# Curing_cab.net
KiCad netlist of a schematic drawn in EAGLE
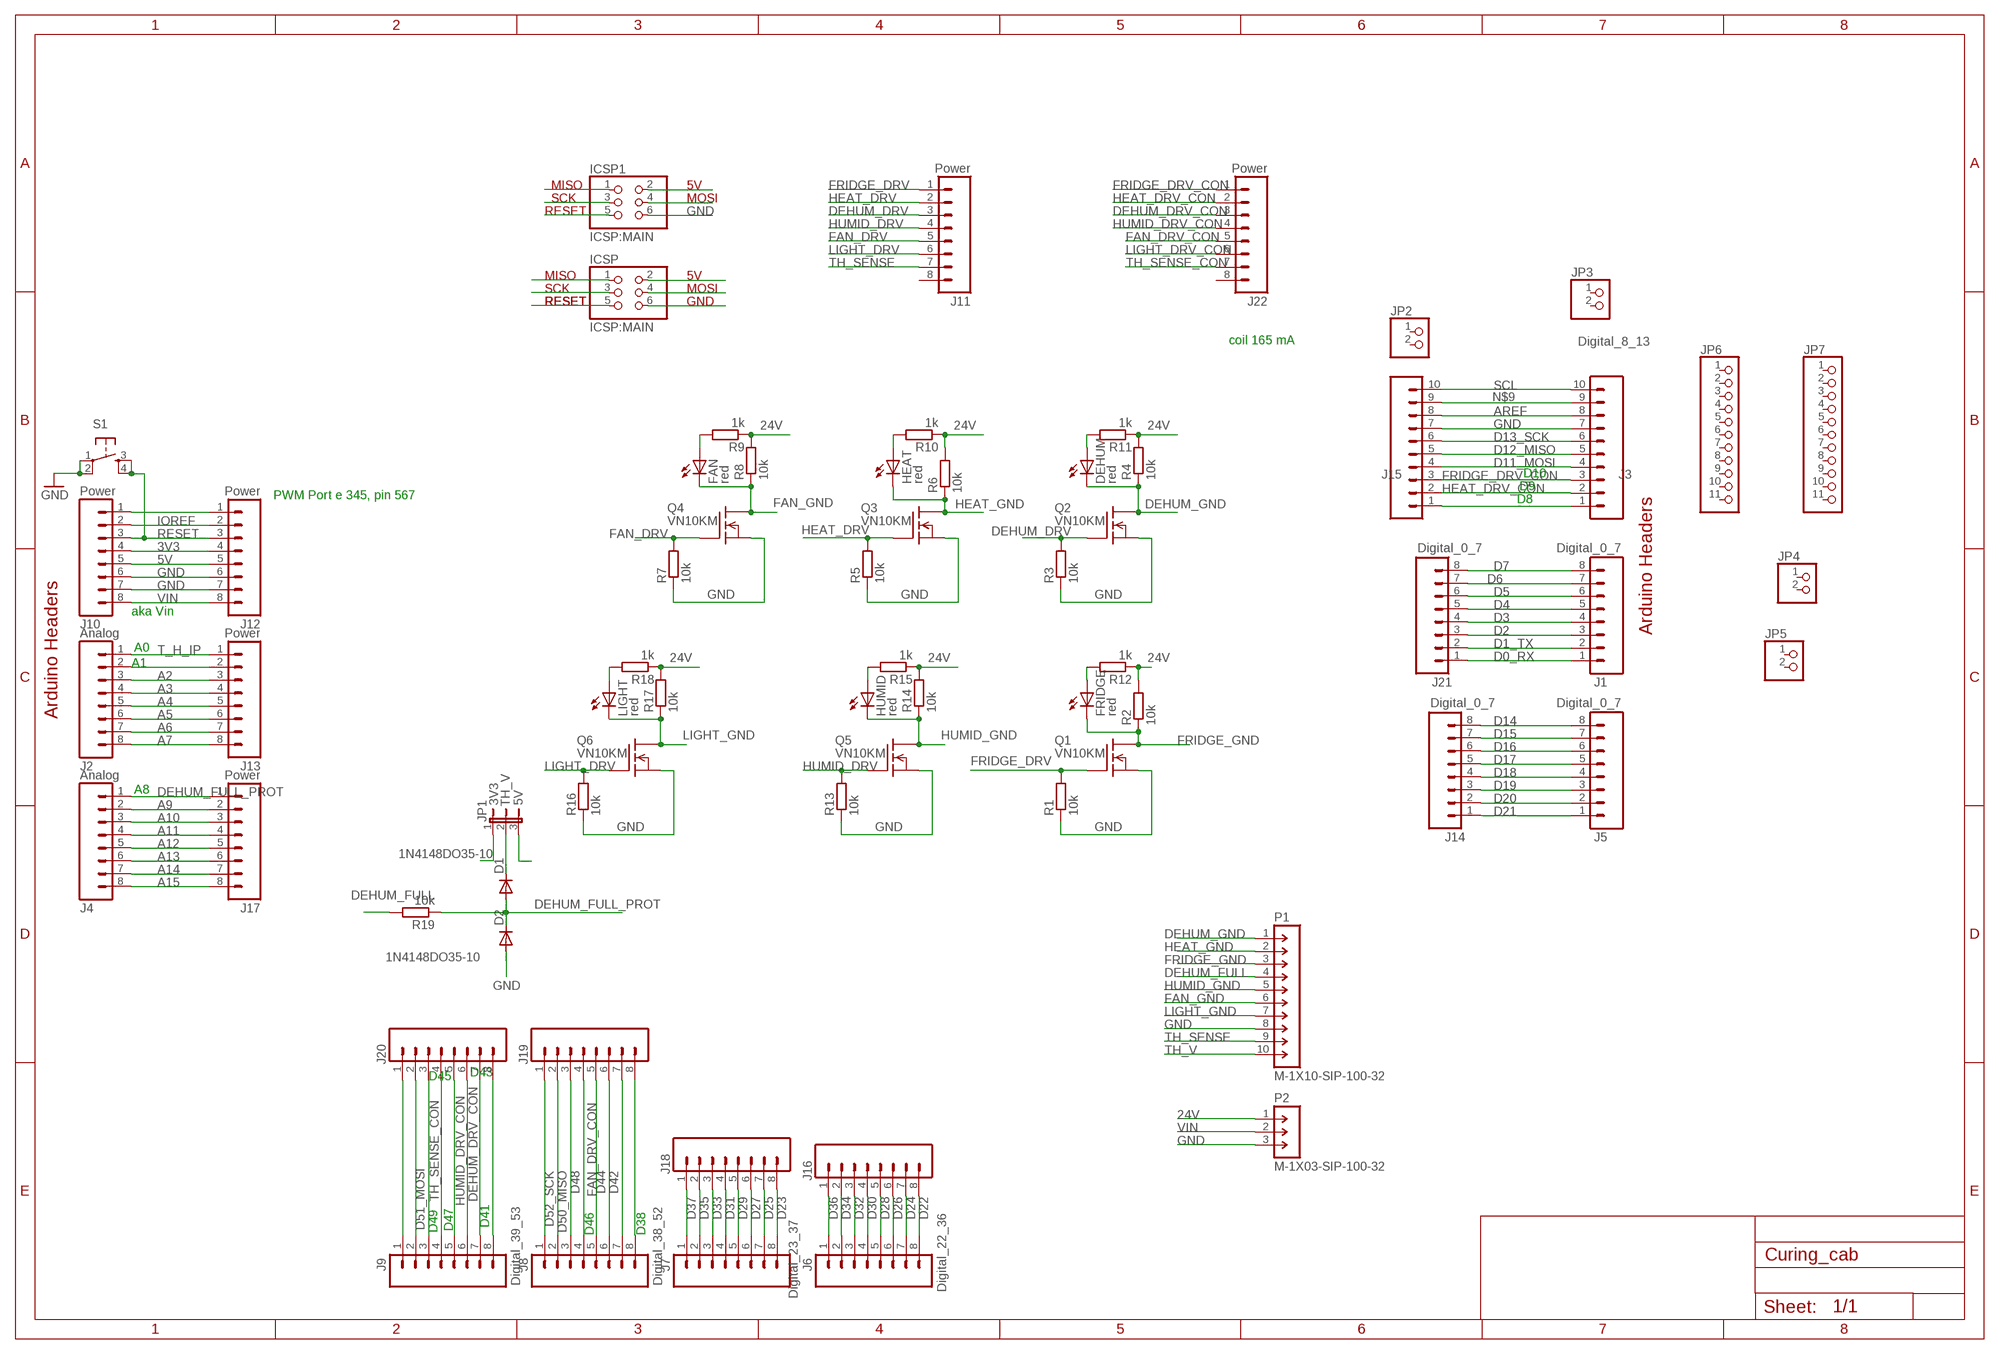
[diagram p0: schematic, sheet 1]

(export (version "E")
  (design (tool "Eeschema 10.0.6"))
  (components
    (comp (ref "D1")
      (value "1N4148DO35-10")
      (footprint "eagle-import:DO35-10")
      (libsource (lib "eagle-import") (part "1N4148DO35-10"))
    )
    (comp (ref "D2")
      (value "1N4148DO35-10")
      (footprint "eagle-import:DO35-10")
      (libsource (lib "eagle-import") (part "1N4148DO35-10"))
    )
    (comp (ref "DEHUM")
      (value "red")
      (footprint "eagle-import:LED3MM")
      (libsource (lib "eagle-import") (part "LED3MM"))
    )
    (comp (ref "FAN")
      (value "red")
      (footprint "eagle-import:LED3MM")
      (libsource (lib "eagle-import") (part "LED3MM"))
    )
    (comp (ref "FRIDGE")
      (value "red")
      (footprint "eagle-import:LED3MM")
      (libsource (lib "eagle-import") (part "LED3MM"))
    )
    (comp (ref "HEAT")
      (value "red")
      (footprint "eagle-import:LED3MM")
      (libsource (lib "eagle-import") (part "LED3MM"))
    )
    (comp (ref "HUMID")
      (value "red")
      (footprint "eagle-import:LED3MM")
      (libsource (lib "eagle-import") (part "LED3MM"))
    )
    (comp (ref "ICSP")
      (value "ICSP:MAIN")
      (footprint "eagle-import:2X03")
      (libsource (lib "eagle-import") (part "PINHD-2X3"))
    )
    (comp (ref "ICSP1")
      (value "ICSP:MAIN")
      (footprint "eagle-import:2X03")
      (libsource (lib "eagle-import") (part "PINHD-2X3"))
    )
    (comp (ref "J1")
      (value "Digital_0_7")
      (footprint "eagle-import:1X08")
      (libsource (lib "eagle-import") (part "M08"))
    )
    (comp (ref "J2")
      (value "Analog")
      (footprint "eagle-import:1X08")
      (libsource (lib "eagle-import") (part "freetronics-master-v1_M08"))
    )
    (comp (ref "J3")
      (value "Digital_8_13")
      (footprint "eagle-import:1X10")
      (libsource (lib "eagle-import") (part "M100.1"))
    )
    (comp (ref "J4")
      (value "Analog")
      (footprint "eagle-import:1X08")
      (libsource (lib "eagle-import") (part "freetronics-master-v1_M08"))
    )
    (comp (ref "J5")
      (value "Digital_0_7")
      (footprint "eagle-import:1X08")
      (libsource (lib "eagle-import") (part "M08"))
    )
    (comp (ref "J6")
      (value "Digital_22_36")
      (footprint "eagle-import:1X08")
      (libsource (lib "eagle-import") (part "M08"))
    )
    (comp (ref "J7")
      (value "Digital_23_37")
      (footprint "eagle-import:1X08")
      (libsource (lib "eagle-import") (part "M08"))
    )
    (comp (ref "J8")
      (value "Digital_38_52")
      (footprint "eagle-import:1X08")
      (libsource (lib "eagle-import") (part "M08"))
    )
    (comp (ref "J9")
      (value "Digital_39_53")
      (footprint "eagle-import:1X08")
      (libsource (lib "eagle-import") (part "M08"))
    )
    (comp (ref "J10")
      (value "Power")
      (footprint "eagle-import:1X08")
      (libsource (lib "eagle-import") (part "freetronics-master-v1_M08"))
    )
    (comp (ref "J11")
      (value "Power")
      (footprint "eagle-import:1X08")
      (libsource (lib "eagle-import") (part "freetronics-master-v1_M08"))
    )
    (comp (ref "J12")
      (value "Power")
      (footprint "eagle-import:1X08")
      (libsource (lib "eagle-import") (part "freetronics-master-v1_M08"))
    )
    (comp (ref "J13")
      (value "Power")
      (footprint "eagle-import:1X08")
      (libsource (lib "eagle-import") (part "freetronics-master-v1_M08"))
    )
    (comp (ref "J14")
      (value "Digital_0_7")
      (footprint "eagle-import:1X08")
      (libsource (lib "eagle-import") (part "M08"))
    )
    (comp (ref "J15")
      (value "Digital_8_13")
      (footprint "eagle-import:1X10")
      (libsource (lib "eagle-import") (part "M100.1"))
    )
    (comp (ref "J16")
      (value "Digital_22_36")
      (footprint "eagle-import:1X08")
      (libsource (lib "eagle-import") (part "M08"))
    )
    (comp (ref "J17")
      (value "Power")
      (footprint "eagle-import:1X08")
      (libsource (lib "eagle-import") (part "freetronics-master-v1_M08"))
    )
    (comp (ref "J18")
      (value "Digital_22_36")
      (footprint "eagle-import:1X08")
      (libsource (lib "eagle-import") (part "M08"))
    )
    (comp (ref "J19")
      (value "Digital_22_36")
      (footprint "eagle-import:1X08")
      (libsource (lib "eagle-import") (part "M08"))
    )
    (comp (ref "J20")
      (value "Digital_22_36")
      (footprint "eagle-import:1X08")
      (libsource (lib "eagle-import") (part "M08"))
    )
    (comp (ref "J21")
      (value "Digital_0_7")
      (footprint "eagle-import:1X08")
      (libsource (lib "eagle-import") (part "M08"))
    )
    (comp (ref "J22")
      (value "Power")
      (footprint "eagle-import:1X08")
      (libsource (lib "eagle-import") (part "freetronics-master-v1_M08"))
    )
    (comp (ref "JP1")
      (value "JP2E")
      (footprint "eagle-import:JP2")
      (libsource (lib "eagle-import") (part "JP2E"))
    )
    (comp (ref "JP2")
      (value "PINHD-1X2")
      (footprint "eagle-import:1X02")
      (libsource (lib "eagle-import") (part "PINHD-1X2"))
    )
    (comp (ref "JP3")
      (value "PINHD-1X2")
      (footprint "eagle-import:1X02")
      (libsource (lib "eagle-import") (part "PINHD-1X2"))
    )
    (comp (ref "JP4")
      (value "PINHD-1X2")
      (footprint "eagle-import:1X02")
      (libsource (lib "eagle-import") (part "PINHD-1X2"))
    )
    (comp (ref "JP5")
      (value "PINHD-1X2")
      (footprint "eagle-import:1X02")
      (libsource (lib "eagle-import") (part "PINHD-1X2"))
    )
    (comp (ref "JP6")
      (value "PINHD-1X11")
      (footprint "eagle-import:1X11")
      (libsource (lib "eagle-import") (part "PINHD-1X11"))
    )
    (comp (ref "JP7")
      (value "PINHD-1X11")
      (footprint "eagle-import:1X11")
      (libsource (lib "eagle-import") (part "PINHD-1X11"))
    )
    (comp (ref "LIGHT")
      (value "red")
      (footprint "eagle-import:LED3MM")
      (libsource (lib "eagle-import") (part "LED3MM"))
    )
    (comp (ref "P1")
      (value "M-1X10-SIP-100-32")
      (footprint "eagle-import:SIP-100-10-32")
      (libsource (lib "eagle-import") (part "M-1X10-SIP-100-32"))
    )
    (comp (ref "P2")
      (value "M-1X03-SIP-100-32")
      (footprint "eagle-import:SIP-100-03-32")
      (libsource (lib "eagle-import") (part "M-1X03-SIP-100-32"))
    )
    (comp (ref "Q1")
      (value "VN10KM")
      (footprint "eagle-import:TO237")
      (libsource (lib "eagle-import") (part "VN10KM"))
    )
    (comp (ref "Q2")
      (value "VN10KM")
      (footprint "eagle-import:TO237")
      (libsource (lib "eagle-import") (part "VN10KM"))
    )
    (comp (ref "Q3")
      (value "VN10KM")
      (footprint "eagle-import:TO237")
      (libsource (lib "eagle-import") (part "VN10KM"))
    )
    (comp (ref "Q4")
      (value "VN10KM")
      (footprint "eagle-import:TO237")
      (libsource (lib "eagle-import") (part "VN10KM"))
    )
    (comp (ref "Q5")
      (value "VN10KM")
      (footprint "eagle-import:TO237")
      (libsource (lib "eagle-import") (part "VN10KM"))
    )
    (comp (ref "Q6")
      (value "VN10KM")
      (footprint "eagle-import:TO237")
      (libsource (lib "eagle-import") (part "VN10KM"))
    )
    (comp (ref "R1")
      (value "10k")
      (footprint "eagle-import:0204_7")
      (libsource (lib "eagle-import") (part "R-EU_0204/7"))
    )
    (comp (ref "R2")
      (value "10k")
      (footprint "eagle-import:0204_7")
      (libsource (lib "eagle-import") (part "R-EU_0204/7"))
    )
    (comp (ref "R3")
      (value "10k")
      (footprint "eagle-import:0204_7")
      (libsource (lib "eagle-import") (part "R-EU_0204/7"))
    )
    (comp (ref "R4")
      (value "10k")
      (footprint "eagle-import:0204_7")
      (libsource (lib "eagle-import") (part "R-EU_0204/7"))
    )
    (comp (ref "R5")
      (value "10k")
      (footprint "eagle-import:0204_7")
      (libsource (lib "eagle-import") (part "R-EU_0204/7"))
    )
    (comp (ref "R6")
      (value "10k")
      (footprint "eagle-import:0204_7")
      (libsource (lib "eagle-import") (part "R-EU_0204/7"))
    )
    (comp (ref "R7")
      (value "10k")
      (footprint "eagle-import:0204_7")
      (libsource (lib "eagle-import") (part "R-EU_0204/7"))
    )
    (comp (ref "R8")
      (value "10k")
      (footprint "eagle-import:0204_7")
      (libsource (lib "eagle-import") (part "R-EU_0204/7"))
    )
    (comp (ref "R9")
      (value "1k")
      (footprint "eagle-import:0204_7")
      (libsource (lib "eagle-import") (part "R-EU_0204/7"))
    )
    (comp (ref "R10")
      (value "1k")
      (footprint "eagle-import:0204_7")
      (libsource (lib "eagle-import") (part "R-EU_0204/7"))
    )
    (comp (ref "R11")
      (value "1k")
      (footprint "eagle-import:0204_7")
      (libsource (lib "eagle-import") (part "R-EU_0204/7"))
    )
    (comp (ref "R12")
      (value "1k")
      (footprint "eagle-import:0204_7")
      (libsource (lib "eagle-import") (part "R-EU_0204/7"))
    )
    (comp (ref "R13")
      (value "10k")
      (footprint "eagle-import:0204_7")
      (libsource (lib "eagle-import") (part "R-EU_0204/7"))
    )
    (comp (ref "R14")
      (value "10k")
      (footprint "eagle-import:0204_7")
      (libsource (lib "eagle-import") (part "R-EU_0204/7"))
    )
    (comp (ref "R15")
      (value "1k")
      (footprint "eagle-import:0204_7")
      (libsource (lib "eagle-import") (part "R-EU_0204/7"))
    )
    (comp (ref "R16")
      (value "10k")
      (footprint "eagle-import:0204_7")
      (libsource (lib "eagle-import") (part "R-EU_0204/7"))
    )
    (comp (ref "R17")
      (value "10k")
      (footprint "eagle-import:0204_7")
      (libsource (lib "eagle-import") (part "R-EU_0204/7"))
    )
    (comp (ref "R18")
      (value "1k")
      (footprint "eagle-import:0204_7")
      (libsource (lib "eagle-import") (part "R-EU_0204/7"))
    )
    (comp (ref "R19")
      (value "10k")
      (footprint "eagle-import:0204_7")
      (libsource (lib "eagle-import") (part "R-EU_0204/7"))
    )
    (comp (ref "S1")
      (value "TAC_SWITCHPTH")
      (footprint "eagle-import:TACTILE-PTH")
      (libsource (lib "eagle-import") (part "TAC_SWITCHPTH"))
    )
  )
  (nets
    (net (code "1") (name "/3V3") (class "Default")
      (node (ref "J10") (pin "4") (pinfunction "4_4") (pintype "passive"))
      (node (ref "J12") (pin "4") (pinfunction "4_4") (pintype "passive"))
      (node (ref "JP1") (pin "1") (pinfunction "1_1") (pintype "passive"))
    )
    (net (code "2") (name "/5V") (class "Default")
      (node (ref "J10") (pin "5") (pinfunction "5_5") (pintype "passive"))
      (node (ref "J12") (pin "5") (pinfunction "5_5") (pintype "passive"))
      (node (ref "JP1") (pin "3") (pinfunction "3_3") (pintype "passive"))
    )
    (net (code "3") (name "/5V_1") (class "Default")
      (node (ref "ICSP") (pin "2") (pinfunction "2_2") (pintype "passive"))
      (node (ref "ICSP1") (pin "2") (pinfunction "2_2") (pintype "passive"))
    )
    (net (code "4") (name "/24V") (class "Default")
      (node (ref "P2") (pin "1") (pinfunction "1_1") (pintype "passive"))
      (node (ref "R10") (pin "1") (pinfunction "1_1") (pintype "passive"))
      (node (ref "R11") (pin "1") (pinfunction "1_1") (pintype "passive"))
      (node (ref "R12") (pin "1") (pinfunction "1_1") (pintype "passive"))
      (node (ref "R14") (pin "2") (pinfunction "2_2") (pintype "passive"))
      (node (ref "R15") (pin "1") (pinfunction "1_1") (pintype "passive"))
      (node (ref "R17") (pin "2") (pinfunction "2_2") (pintype "passive"))
      (node (ref "R18") (pin "1") (pinfunction "1_1") (pintype "passive"))
      (node (ref "R2") (pin "2") (pinfunction "2_2") (pintype "passive"))
      (node (ref "R4") (pin "2") (pinfunction "2_2") (pintype "passive"))
      (node (ref "R6") (pin "2") (pinfunction "2_2") (pintype "passive"))
      (node (ref "R8") (pin "2") (pinfunction "2_2") (pintype "passive"))
      (node (ref "R9") (pin "1") (pinfunction "1_1") (pintype "passive"))
    )
    (net (code "5") (name "/A2") (class "Default")
      (node (ref "J13") (pin "3") (pinfunction "3_3") (pintype "passive"))
      (node (ref "J2") (pin "3") (pinfunction "3_3") (pintype "passive"))
    )
    (net (code "6") (name "/A3") (class "Default")
      (node (ref "J13") (pin "4") (pinfunction "4_4") (pintype "passive"))
      (node (ref "J2") (pin "4") (pinfunction "4_4") (pintype "passive"))
    )
    (net (code "7") (name "/A4") (class "Default")
      (node (ref "J13") (pin "5") (pinfunction "5_5") (pintype "passive"))
      (node (ref "J2") (pin "5") (pinfunction "5_5") (pintype "passive"))
    )
    (net (code "8") (name "/A5") (class "Default")
      (node (ref "J13") (pin "6") (pinfunction "6_6") (pintype "passive"))
      (node (ref "J2") (pin "6") (pinfunction "6_6") (pintype "passive"))
    )
    (net (code "9") (name "/A6") (class "Default")
      (node (ref "J13") (pin "7") (pinfunction "7_7") (pintype "passive"))
      (node (ref "J2") (pin "7") (pinfunction "7_7") (pintype "passive"))
    )
    (net (code "10") (name "/A7") (class "Default")
      (node (ref "J13") (pin "8") (pinfunction "8_8") (pintype "passive"))
      (node (ref "J2") (pin "8") (pinfunction "8_8") (pintype "passive"))
    )
    (net (code "11") (name "/A9") (class "Default")
      (node (ref "J17") (pin "2") (pinfunction "2_2") (pintype "passive"))
      (node (ref "J4") (pin "2") (pinfunction "2_2") (pintype "passive"))
    )
    (net (code "12") (name "/A10") (class "Default")
      (node (ref "J17") (pin "3") (pinfunction "3_3") (pintype "passive"))
      (node (ref "J4") (pin "3") (pinfunction "3_3") (pintype "passive"))
    )
    (net (code "13") (name "/A11") (class "Default")
      (node (ref "J17") (pin "4") (pinfunction "4_4") (pintype "passive"))
      (node (ref "J4") (pin "4") (pinfunction "4_4") (pintype "passive"))
    )
    (net (code "14") (name "/A12") (class "Default")
      (node (ref "J17") (pin "5") (pinfunction "5_5") (pintype "passive"))
      (node (ref "J4") (pin "5") (pinfunction "5_5") (pintype "passive"))
    )
    (net (code "15") (name "/A13") (class "Default")
      (node (ref "J17") (pin "6") (pinfunction "6_6") (pintype "passive"))
      (node (ref "J4") (pin "6") (pinfunction "6_6") (pintype "passive"))
    )
    (net (code "16") (name "/A14") (class "Default")
      (node (ref "J17") (pin "7") (pinfunction "7_7") (pintype "passive"))
      (node (ref "J4") (pin "7") (pinfunction "7_7") (pintype "passive"))
    )
    (net (code "17") (name "/A15") (class "Default")
      (node (ref "J17") (pin "8") (pinfunction "8_8") (pintype "passive"))
      (node (ref "J4") (pin "8") (pinfunction "8_8") (pintype "passive"))
    )
    (net (code "18") (name "/AREF") (class "Default")
      (node (ref "J15") (pin "8") (pinfunction "8_8") (pintype "passive"))
      (node (ref "J3") (pin "8") (pinfunction "8_8") (pintype "passive"))
    )
    (net (code "19") (name "/D0_RX") (class "Default")
      (node (ref "J1") (pin "1") (pinfunction "1_1") (pintype "passive"))
      (node (ref "J21") (pin "1") (pinfunction "1_1") (pintype "passive"))
    )
    (net (code "20") (name "/D1_TX") (class "Default")
      (node (ref "J1") (pin "2") (pinfunction "2_2") (pintype "passive"))
      (node (ref "J21") (pin "2") (pinfunction "2_2") (pintype "passive"))
    )
    (net (code "21") (name "/D2") (class "Default")
      (node (ref "J1") (pin "3") (pinfunction "3_3") (pintype "passive"))
      (node (ref "J21") (pin "3") (pinfunction "3_3") (pintype "passive"))
    )
    (net (code "22") (name "/D3") (class "Default")
      (node (ref "J1") (pin "4") (pinfunction "4_4") (pintype "passive"))
      (node (ref "J21") (pin "4") (pinfunction "4_4") (pintype "passive"))
    )
    (net (code "23") (name "/D4") (class "Default")
      (node (ref "J1") (pin "5") (pinfunction "5_5") (pintype "passive"))
      (node (ref "J21") (pin "5") (pinfunction "5_5") (pintype "passive"))
    )
    (net (code "24") (name "/D5") (class "Default")
      (node (ref "J1") (pin "6") (pinfunction "6_6") (pintype "passive"))
      (node (ref "J21") (pin "6") (pinfunction "6_6") (pintype "passive"))
    )
    (net (code "25") (name "/D6") (class "Default")
      (node (ref "J1") (pin "7") (pinfunction "7_7") (pintype "passive"))
      (node (ref "J21") (pin "7") (pinfunction "7_7") (pintype "passive"))
    )
    (net (code "26") (name "/D7") (class "Default")
      (node (ref "J1") (pin "8") (pinfunction "8_8") (pintype "passive"))
      (node (ref "J21") (pin "8") (pinfunction "8_8") (pintype "passive"))
    )
    (net (code "27") (name "/D11_MOSI") (class "Default")
      (node (ref "J15") (pin "4") (pinfunction "4_4") (pintype "passive"))
      (node (ref "J3") (pin "4") (pinfunction "4_4") (pintype "passive"))
    )
    (net (code "28") (name "/D12_MISO") (class "Default")
      (node (ref "J15") (pin "5") (pinfunction "5_5") (pintype "passive"))
      (node (ref "J3") (pin "5") (pinfunction "5_5") (pintype "passive"))
    )
    (net (code "29") (name "/D13_SCK") (class "Default")
      (node (ref "J15") (pin "6") (pinfunction "6_6") (pintype "passive"))
      (node (ref "J3") (pin "6") (pinfunction "6_6") (pintype "passive"))
    )
    (net (code "30") (name "/D14") (class "Default")
      (node (ref "J14") (pin "8") (pinfunction "8_8") (pintype "passive"))
      (node (ref "J5") (pin "8") (pinfunction "8_8") (pintype "passive"))
    )
    (net (code "31") (name "/D15") (class "Default")
      (node (ref "J14") (pin "7") (pinfunction "7_7") (pintype "passive"))
      (node (ref "J5") (pin "7") (pinfunction "7_7") (pintype "passive"))
    )
    (net (code "32") (name "/D16") (class "Default")
      (node (ref "J14") (pin "6") (pinfunction "6_6") (pintype "passive"))
      (node (ref "J5") (pin "6") (pinfunction "6_6") (pintype "passive"))
    )
    (net (code "33") (name "/D17") (class "Default")
      (node (ref "J14") (pin "5") (pinfunction "5_5") (pintype "passive"))
      (node (ref "J5") (pin "5") (pinfunction "5_5") (pintype "passive"))
    )
    (net (code "34") (name "/D18") (class "Default")
      (node (ref "J14") (pin "4") (pinfunction "4_4") (pintype "passive"))
      (node (ref "J5") (pin "4") (pinfunction "4_4") (pintype "passive"))
    )
    (net (code "35") (name "/D19") (class "Default")
      (node (ref "J14") (pin "3") (pinfunction "3_3") (pintype "passive"))
      (node (ref "J5") (pin "3") (pinfunction "3_3") (pintype "passive"))
    )
    (net (code "36") (name "/D20") (class "Default")
      (node (ref "J14") (pin "2") (pinfunction "2_2") (pintype "passive"))
      (node (ref "J5") (pin "2") (pinfunction "2_2") (pintype "passive"))
    )
    (net (code "37") (name "/D21") (class "Default")
      (node (ref "J14") (pin "1") (pinfunction "1_1") (pintype "passive"))
      (node (ref "J5") (pin "1") (pinfunction "1_1") (pintype "passive"))
    )
    (net (code "38") (name "/D22") (class "Default")
      (node (ref "J16") (pin "8") (pinfunction "8_8") (pintype "passive"))
      (node (ref "J6") (pin "8") (pinfunction "8_8") (pintype "passive"))
    )
    (net (code "39") (name "/D23") (class "Default")
      (node (ref "J18") (pin "8") (pinfunction "8_8") (pintype "passive"))
      (node (ref "J7") (pin "8") (pinfunction "8_8") (pintype "passive"))
    )
    (net (code "40") (name "/D24") (class "Default")
      (node (ref "J16") (pin "7") (pinfunction "7_7") (pintype "passive"))
      (node (ref "J6") (pin "7") (pinfunction "7_7") (pintype "passive"))
    )
    (net (code "41") (name "/D25") (class "Default")
      (node (ref "J18") (pin "7") (pinfunction "7_7") (pintype "passive"))
      (node (ref "J7") (pin "7") (pinfunction "7_7") (pintype "passive"))
    )
    (net (code "42") (name "/D26") (class "Default")
      (node (ref "J16") (pin "6") (pinfunction "6_6") (pintype "passive"))
      (node (ref "J6") (pin "6") (pinfunction "6_6") (pintype "passive"))
    )
    (net (code "43") (name "/D27") (class "Default")
      (node (ref "J18") (pin "6") (pinfunction "6_6") (pintype "passive"))
      (node (ref "J7") (pin "6") (pinfunction "6_6") (pintype "passive"))
    )
    (net (code "44") (name "/D28") (class "Default")
      (node (ref "J16") (pin "5") (pinfunction "5_5") (pintype "passive"))
      (node (ref "J6") (pin "5") (pinfunction "5_5") (pintype "passive"))
    )
    (net (code "45") (name "/D29") (class "Default")
      (node (ref "J18") (pin "5") (pinfunction "5_5") (pintype "passive"))
      (node (ref "J7") (pin "5") (pinfunction "5_5") (pintype "passive"))
    )
    (net (code "46") (name "/D30") (class "Default")
      (node (ref "J16") (pin "4") (pinfunction "4_4") (pintype "passive"))
      (node (ref "J6") (pin "4") (pinfunction "4_4") (pintype "passive"))
    )
    (net (code "47") (name "/D31") (class "Default")
      (node (ref "J18") (pin "4") (pinfunction "4_4") (pintype "passive"))
      (node (ref "J7") (pin "4") (pinfunction "4_4") (pintype "passive"))
    )
    (net (code "48") (name "/D32") (class "Default")
      (node (ref "J16") (pin "3") (pinfunction "3_3") (pintype "passive"))
      (node (ref "J6") (pin "3") (pinfunction "3_3") (pintype "passive"))
    )
    (net (code "49") (name "/D33") (class "Default")
      (node (ref "J18") (pin "3") (pinfunction "3_3") (pintype "passive"))
      (node (ref "J7") (pin "3") (pinfunction "3_3") (pintype "passive"))
    )
    (net (code "50") (name "/D34") (class "Default")
      (node (ref "J16") (pin "2") (pinfunction "2_2") (pintype "passive"))
      (node (ref "J6") (pin "2") (pinfunction "2_2") (pintype "passive"))
    )
    (net (code "51") (name "/D35") (class "Default")
      (node (ref "J18") (pin "2") (pinfunction "2_2") (pintype "passive"))
      (node (ref "J7") (pin "2") (pinfunction "2_2") (pintype "passive"))
    )
    (net (code "52") (name "/D36") (class "Default")
      (node (ref "J16") (pin "1") (pinfunction "1_1") (pintype "passive"))
      (node (ref "J6") (pin "1") (pinfunction "1_1") (pintype "passive"))
    )
    (net (code "53") (name "/D37") (class "Default")
      (node (ref "J18") (pin "1") (pinfunction "1_1") (pintype "passive"))
      (node (ref "J7") (pin "1") (pinfunction "1_1") (pintype "passive"))
    )
    (net (code "54") (name "/D42") (class "Default")
      (node (ref "J19") (pin "6") (pinfunction "6_6") (pintype "passive"))
      (node (ref "J8") (pin "6") (pinfunction "6_6") (pintype "passive"))
    )
    (net (code "55") (name "/D44") (class "Default")
      (node (ref "J19") (pin "5") (pinfunction "5_5") (pintype "passive"))
      (node (ref "J8") (pin "5") (pinfunction "5_5") (pintype "passive"))
    )
    (net (code "56") (name "/D48") (class "Default")
      (node (ref "J19") (pin "3") (pinfunction "3_3") (pintype "passive"))
      (node (ref "J8") (pin "3") (pinfunction "3_3") (pintype "passive"))
    )
    (net (code "57") (name "/D50_MISO") (class "Default")
      (node (ref "J19") (pin "2") (pinfunction "2_2") (pintype "passive"))
      (node (ref "J8") (pin "2") (pinfunction "2_2") (pintype "passive"))
    )
    (net (code "58") (name "/D51_MOSI") (class "Default")
      (node (ref "J20") (pin "2") (pinfunction "2_2") (pintype "passive"))
      (node (ref "J9") (pin "2") (pinfunction "2_2") (pintype "passive"))
    )
    (net (code "59") (name "/D52_SCK") (class "Default")
      (node (ref "J19") (pin "1") (pinfunction "1_1") (pintype "passive"))
      (node (ref "J8") (pin "1") (pinfunction "1_1") (pintype "passive"))
    )
    (net (code "60") (name "/DEHUM_DRV") (class "Default")
      (node (ref "J11") (pin "3") (pinfunction "3_3") (pintype "passive"))
      (node (ref "Q2") (pin "2") (pinfunction "G_2") (pintype "passive"))
      (node (ref "R3") (pin "2") (pinfunction "2_2") (pintype "passive"))
    )
    (net (code "61") (name "/DEHUM_DRV_CON") (class "Default")
      (node (ref "J20") (pin "6") (pinfunction "6_6") (pintype "passive"))
      (node (ref "J22") (pin "3") (pinfunction "3_3") (pintype "passive"))
      (node (ref "J9") (pin "6") (pinfunction "6_6") (pintype "passive"))
    )
    (net (code "62") (name "/DEHUM_FULL") (class "Default")
      (node (ref "P1") (pin "4") (pinfunction "4_4") (pintype "passive"))
      (node (ref "R19") (pin "2") (pinfunction "2_2") (pintype "passive"))
    )
    (net (code "63") (name "/DEHUM_FULL_PROT") (class "Default")
      (node (ref "D1") (pin "A") (pinfunction "A_A") (pintype "passive"))
      (node (ref "D2") (pin "C") (pinfunction "C_C") (pintype "passive"))
      (node (ref "J17") (pin "1") (pinfunction "1_1") (pintype "passive"))
      (node (ref "J4") (pin "1") (pinfunction "1_1") (pintype "passive"))
      (node (ref "R19") (pin "1") (pinfunction "1_1") (pintype "passive"))
    )
    (net (code "64") (name "/DEHUM_GND") (class "Default")
      (node (ref "DEHUM") (pin "K") (pinfunction "C_K") (pintype "passive"))
      (node (ref "P1") (pin "1") (pinfunction "1_1") (pintype "passive"))
      (node (ref "Q2") (pin "1") (pinfunction "D_1") (pintype "passive"))
      (node (ref "R4") (pin "1") (pinfunction "1_1") (pintype "passive"))
    )
    (net (code "65") (name "/FAN_DRV") (class "Default")
      (node (ref "J11") (pin "5") (pinfunction "5_5") (pintype "passive"))
      (node (ref "Q4") (pin "2") (pinfunction "G_2") (pintype "passive"))
      (node (ref "R7") (pin "2") (pinfunction "2_2") (pintype "passive"))
    )
    (net (code "66") (name "/FAN_DRV_CON") (class "Default")
      (node (ref "J19") (pin "4") (pinfunction "4_4") (pintype "passive"))
      (node (ref "J22") (pin "5") (pinfunction "5_5") (pintype "passive"))
      (node (ref "J8") (pin "4") (pinfunction "4_4") (pintype "passive"))
    )
    (net (code "67") (name "/FAN_GND") (class "Default")
      (node (ref "FAN") (pin "K") (pinfunction "C_K") (pintype "passive"))
      (node (ref "P1") (pin "6") (pinfunction "6_6") (pintype "passive"))
      (node (ref "Q4") (pin "1") (pinfunction "D_1") (pintype "passive"))
      (node (ref "R8") (pin "1") (pinfunction "1_1") (pintype "passive"))
    )
    (net (code "68") (name "/FRIDGE_DRV") (class "Default")
      (node (ref "J11") (pin "1") (pinfunction "1_1") (pintype "passive"))
      (node (ref "Q1") (pin "2") (pinfunction "G_2") (pintype "passive"))
      (node (ref "R1") (pin "2") (pinfunction "2_2") (pintype "passive"))
    )
    (net (code "69") (name "/FRIDGE_DRV_CON") (class "Default")
      (node (ref "J15") (pin "3") (pinfunction "3_3") (pintype "passive"))
      (node (ref "J22") (pin "1") (pinfunction "1_1") (pintype "passive"))
      (node (ref "J3") (pin "3") (pinfunction "3_3") (pintype "passive"))
    )
    (net (code "70") (name "/FRIDGE_GND") (class "Default")
      (node (ref "FRIDGE") (pin "K") (pinfunction "C_K") (pintype "passive"))
      (node (ref "P1") (pin "3") (pinfunction "3_3") (pintype "passive"))
      (node (ref "Q1") (pin "1") (pinfunction "D_1") (pintype "passive"))
      (node (ref "R2") (pin "1") (pinfunction "1_1") (pintype "passive"))
    )
    (net (code "71") (name "/HEAT_DRV") (class "Default")
      (node (ref "J11") (pin "2") (pinfunction "2_2") (pintype "passive"))
      (node (ref "Q3") (pin "2") (pinfunction "G_2") (pintype "passive"))
      (node (ref "R5") (pin "2") (pinfunction "2_2") (pintype "passive"))
    )
    (net (code "72") (name "/HEAT_DRV_CON") (class "Default")
      (node (ref "J15") (pin "2") (pinfunction "2_2") (pintype "passive"))
      (node (ref "J22") (pin "2") (pinfunction "2_2") (pintype "passive"))
      (node (ref "J3") (pin "2") (pinfunction "2_2") (pintype "passive"))
    )
    (net (code "73") (name "/HEAT_GND") (class "Default")
      (node (ref "HEAT") (pin "K") (pinfunction "C_K") (pintype "passive"))
      (node (ref "P1") (pin "2") (pinfunction "2_2") (pintype "passive"))
      (node (ref "Q3") (pin "1") (pinfunction "D_1") (pintype "passive"))
      (node (ref "R6") (pin "1") (pinfunction "1_1") (pintype "passive"))
    )
    (net (code "74") (name "/HUMID_DRV") (class "Default")
      (node (ref "J11") (pin "4") (pinfunction "4_4") (pintype "passive"))
      (node (ref "Q5") (pin "2") (pinfunction "G_2") (pintype "passive"))
      (node (ref "R13") (pin "2") (pinfunction "2_2") (pintype "passive"))
    )
    (net (code "75") (name "/HUMID_DRV_CON") (class "Default")
      (node (ref "J20") (pin "5") (pinfunction "5_5") (pintype "passive"))
      (node (ref "J22") (pin "4") (pinfunction "4_4") (pintype "passive"))
      (node (ref "J9") (pin "5") (pinfunction "5_5") (pintype "passive"))
    )
    (net (code "76") (name "/HUMID_GND") (class "Default")
      (node (ref "HUMID") (pin "K") (pinfunction "C_K") (pintype "passive"))
      (node (ref "P1") (pin "5") (pinfunction "5_5") (pintype "passive"))
      (node (ref "Q5") (pin "1") (pinfunction "D_1") (pintype "passive"))
      (node (ref "R14") (pin "1") (pinfunction "1_1") (pintype "passive"))
    )
    (net (code "77") (name "/IOREF") (class "Default")
      (node (ref "J10") (pin "2") (pinfunction "2_2") (pintype "passive"))
      (node (ref "J12") (pin "2") (pinfunction "2_2") (pintype "passive"))
    )
    (net (code "78") (name "/LIGHT_DRV") (class "Default")
      (node (ref "J11") (pin "6") (pinfunction "6_6") (pintype "passive"))
      (node (ref "Q6") (pin "2") (pinfunction "G_2") (pintype "passive"))
      (node (ref "R16") (pin "2") (pinfunction "2_2") (pintype "passive"))
    )
    (net (code "79") (name "/LIGHT_DRV_CON") (class "Default")
      (node (ref "J20") (pin "4") (pinfunction "4_4") (pintype "passive"))
      (node (ref "J22") (pin "6") (pinfunction "6_6") (pintype "passive"))
      (node (ref "J9") (pin "4") (pinfunction "4_4") (pintype "passive"))
    )
    (net (code "80") (name "/LIGHT_GND") (class "Default")
      (node (ref "LIGHT") (pin "K") (pinfunction "C_K") (pintype "passive"))
      (node (ref "P1") (pin "7") (pinfunction "7_7") (pintype "passive"))
      (node (ref "Q6") (pin "1") (pinfunction "D_1") (pintype "passive"))
      (node (ref "R17") (pin "1") (pinfunction "1_1") (pintype "passive"))
    )
    (net (code "81") (name "/MISO_1") (class "Default")
      (node (ref "ICSP") (pin "1") (pinfunction "1_1") (pintype "passive"))
      (node (ref "ICSP1") (pin "1") (pinfunction "1_1") (pintype "passive"))
    )
    (net (code "82") (name "/MOSI_1") (class "Default")
      (node (ref "ICSP") (pin "4") (pinfunction "4_4") (pintype "passive"))
      (node (ref "ICSP1") (pin "4") (pinfunction "4_4") (pintype "passive"))
    )
    (net (code "83") (name "/N$9") (class "Default")
      (node (ref "J15") (pin "9") (pinfunction "9_9") (pintype "passive"))
      (node (ref "J3") (pin "9") (pinfunction "9_9") (pintype "passive"))
    )
    (net (code "84") (name "/RESET") (class "Default")
      (node (ref "J10") (pin "3") (pinfunction "3_3") (pintype "passive"))
      (node (ref "J12") (pin "3") (pinfunction "3_3") (pintype "passive"))
      (node (ref "S1") (pin "3") (pinfunction "3_3") (pintype "passive"))
      (node (ref "S1") (pin "4") (pinfunction "4_4") (pintype "passive"))
    )
    (net (code "85") (name "/RESET_1") (class "Default")
      (node (ref "ICSP") (pin "5") (pinfunction "5_5") (pintype "passive"))
      (node (ref "ICSP1") (pin "5") (pinfunction "5_5") (pintype "passive"))
    )
    (net (code "86") (name "/SCK_1") (class "Default")
      (node (ref "ICSP") (pin "3") (pinfunction "3_3") (pintype "passive"))
      (node (ref "ICSP1") (pin "3") (pinfunction "3_3") (pintype "passive"))
    )
    (net (code "87") (name "/SCL") (class "Default")
      (node (ref "J15") (pin "10") (pinfunction "10_10") (pintype "passive"))
      (node (ref "J3") (pin "10") (pinfunction "10_10") (pintype "passive"))
    )
    (net (code "88") (name "/TH_SENSE") (class "Default")
      (node (ref "J11") (pin "7") (pinfunction "7_7") (pintype "passive"))
      (node (ref "P1") (pin "9") (pinfunction "9_9") (pintype "passive"))
    )
    (net (code "89") (name "/TH_SENSE_CON") (class "Default")
      (node (ref "J20") (pin "3") (pinfunction "3_3") (pintype "passive"))
      (node (ref "J22") (pin "7") (pinfunction "7_7") (pintype "passive"))
      (node (ref "J9") (pin "3") (pinfunction "3_3") (pintype "passive"))
    )
    (net (code "90") (name "/TH_V") (class "Default")
      (node (ref "D1") (pin "C") (pinfunction "C_C") (pintype "passive"))
      (node (ref "JP1") (pin "2") (pinfunction "2_2") (pintype "passive"))
      (node (ref "P1") (pin "10") (pinfunction "10_10") (pintype "passive"))
    )
    (net (code "91") (name "/T_H_IP") (class "Default")
      (node (ref "J13") (pin "1") (pinfunction "1_1") (pintype "passive"))
      (node (ref "J2") (pin "1") (pinfunction "1_1") (pintype "passive"))
    )
    (net (code "92") (name "/VIN") (class "Default")
      (node (ref "J10") (pin "8") (pinfunction "8_8") (pintype "passive"))
      (node (ref "J12") (pin "8") (pinfunction "8_8") (pintype "passive"))
      (node (ref "P2") (pin "2") (pinfunction "2_2") (pintype "passive"))
    )
    (net (code "93") (name "GND") (class "Default")
      (node (ref "D2") (pin "A") (pinfunction "A_A") (pintype "passive"))
      (node (ref "ICSP") (pin "6") (pinfunction "6_6") (pintype "passive"))
      (node (ref "ICSP1") (pin "6") (pinfunction "6_6") (pintype "passive"))
      (node (ref "J10") (pin "6") (pinfunction "6_6") (pintype "passive"))
      (node (ref "J10") (pin "7") (pinfunction "7_7") (pintype "passive"))
      (node (ref "J12") (pin "6") (pinfunction "6_6") (pintype "passive"))
      (node (ref "J12") (pin "7") (pinfunction "7_7") (pintype "passive"))
      (node (ref "J15") (pin "7") (pinfunction "7_7") (pintype "passive"))
      (node (ref "J3") (pin "7") (pinfunction "7_7") (pintype "passive"))
      (node (ref "P1") (pin "8") (pinfunction "8_8") (pintype "passive"))
      (node (ref "P2") (pin "3") (pinfunction "3_3") (pintype "passive"))
      (node (ref "Q1") (pin "3") (pinfunction "S_3") (pintype "passive"))
      (node (ref "Q2") (pin "3") (pinfunction "S_3") (pintype "passive"))
      (node (ref "Q3") (pin "3") (pinfunction "S_3") (pintype "passive"))
      (node (ref "Q4") (pin "3") (pinfunction "S_3") (pintype "passive"))
      (node (ref "Q5") (pin "3") (pinfunction "S_3") (pintype "passive"))
      (node (ref "Q6") (pin "3") (pinfunction "S_3") (pintype "passive"))
      (node (ref "R1") (pin "1") (pinfunction "1_1") (pintype "passive"))
      (node (ref "R13") (pin "1") (pinfunction "1_1") (pintype "passive"))
      (node (ref "R16") (pin "1") (pinfunction "1_1") (pintype "passive"))
      (node (ref "R3") (pin "1") (pinfunction "1_1") (pintype "passive"))
      (node (ref "R5") (pin "1") (pinfunction "1_1") (pintype "passive"))
      (node (ref "R7") (pin "1") (pinfunction "1_1") (pintype "passive"))
      (node (ref "S1") (pin "1") (pinfunction "1_1") (pintype "passive"))
      (node (ref "S1") (pin "2") (pinfunction "2_2") (pintype "passive"))
    )
    (net (code "94") (name "Net-(DEHUM-PadA)") (class "Default")
      (node (ref "DEHUM") (pin "A") (pinfunction "A_A") (pintype "passive"))
      (node (ref "R11") (pin "2") (pinfunction "2_2") (pintype "passive"))
    )
    (net (code "95") (name "Net-(FAN-PadA)") (class "Default")
      (node (ref "FAN") (pin "A") (pinfunction "A_A") (pintype "passive"))
      (node (ref "R9") (pin "2") (pinfunction "2_2") (pintype "passive"))
    )
    (net (code "96") (name "Net-(FRIDGE-PadA)") (class "Default")
      (node (ref "FRIDGE") (pin "A") (pinfunction "A_A") (pintype "passive"))
      (node (ref "R12") (pin "2") (pinfunction "2_2") (pintype "passive"))
    )
    (net (code "97") (name "Net-(HEAT-PadA)") (class "Default")
      (node (ref "HEAT") (pin "A") (pinfunction "A_A") (pintype "passive"))
      (node (ref "R10") (pin "2") (pinfunction "2_2") (pintype "passive"))
    )
    (net (code "98") (name "Net-(HUMID-PadA)") (class "Default")
      (node (ref "HUMID") (pin "A") (pinfunction "A_A") (pintype "passive"))
      (node (ref "R15") (pin "2") (pinfunction "2_2") (pintype "passive"))
    )
    (net (code "99") (name "Net-(J10-Pad1)") (class "Default")
      (node (ref "J10") (pin "1") (pinfunction "1_1") (pintype "passive"))
      (node (ref "J12") (pin "1") (pinfunction "1_1") (pintype "passive"))
    )
    (net (code "100") (name "Net-(J13-Pad2)") (class "Default")
      (node (ref "J13") (pin "2") (pinfunction "2_2") (pintype "passive"))
      (node (ref "J2") (pin "2") (pinfunction "2_2") (pintype "passive"))
    )
    (net (code "101") (name "Net-(J15-Pad1)") (class "Default")
      (node (ref "J15") (pin "1") (pinfunction "1_1") (pintype "passive"))
      (node (ref "J3") (pin "1") (pinfunction "1_1") (pintype "passive"))
    )
    (net (code "102") (name "Net-(J19-Pad7)") (class "Default")
      (node (ref "J19") (pin "7") (pinfunction "7_7") (pintype "passive"))
      (node (ref "J8") (pin "7") (pinfunction "7_7") (pintype "passive"))
    )
    (net (code "103") (name "Net-(J19-Pad8)") (class "Default")
      (node (ref "J19") (pin "8") (pinfunction "8_8") (pintype "passive"))
      (node (ref "J8") (pin "8") (pinfunction "8_8") (pintype "passive"))
    )
    (net (code "104") (name "Net-(J20-Pad1)") (class "Default")
      (node (ref "J20") (pin "1") (pinfunction "1_1") (pintype "passive"))
      (node (ref "J9") (pin "1") (pinfunction "1_1") (pintype "passive"))
    )
    (net (code "105") (name "Net-(J20-Pad7)") (class "Default")
      (node (ref "J20") (pin "7") (pinfunction "7_7") (pintype "passive"))
      (node (ref "J9") (pin "7") (pinfunction "7_7") (pintype "passive"))
    )
    (net (code "106") (name "Net-(J20-Pad8)") (class "Default")
      (node (ref "J20") (pin "8") (pinfunction "8_8") (pintype "passive"))
      (node (ref "J9") (pin "8") (pinfunction "8_8") (pintype "passive"))
    )
    (net (code "107") (name "Net-(LIGHT-PadA)") (class "Default")
      (node (ref "LIGHT") (pin "A") (pinfunction "A_A") (pintype "passive"))
      (node (ref "R18") (pin "2") (pinfunction "2_2") (pintype "passive"))
    )
    (net (code "108") (name "unconnected-(J11-Pad8)") (class "Default")
      (node (ref "J11") (pin "8") (pinfunction "8_8") (pintype "passive"))
    )
    (net (code "109") (name "unconnected-(J22-Pad8)") (class "Default")
      (node (ref "J22") (pin "8") (pinfunction "8_8") (pintype "passive"))
    )
    (net (code "110") (name "unconnected-(JP2-Pad1)") (class "Default")
      (node (ref "JP2") (pin "1") (pinfunction "1_1") (pintype "passive"))
    )
    (net (code "111") (name "unconnected-(JP2-Pad2)") (class "Default")
      (node (ref "JP2") (pin "2") (pinfunction "2_2") (pintype "passive"))
    )
    (net (code "112") (name "unconnected-(JP3-Pad1)") (class "Default")
      (node (ref "JP3") (pin "1") (pinfunction "1_1") (pintype "passive"))
    )
    (net (code "113") (name "unconnected-(JP3-Pad2)") (class "Default")
      (node (ref "JP3") (pin "2") (pinfunction "2_2") (pintype "passive"))
    )
    (net (code "114") (name "unconnected-(JP4-Pad1)") (class "Default")
      (node (ref "JP4") (pin "1") (pinfunction "1_1") (pintype "passive"))
    )
    (net (code "115") (name "unconnected-(JP4-Pad2)") (class "Default")
      (node (ref "JP4") (pin "2") (pinfunction "2_2") (pintype "passive"))
    )
    (net (code "116") (name "unconnected-(JP5-Pad1)") (class "Default")
      (node (ref "JP5") (pin "1") (pinfunction "1_1") (pintype "passive"))
    )
    (net (code "117") (name "unconnected-(JP5-Pad2)") (class "Default")
      (node (ref "JP5") (pin "2") (pinfunction "2_2") (pintype "passive"))
    )
    (net (code "118") (name "unconnected-(JP6-Pad1)") (class "Default")
      (node (ref "JP6") (pin "1") (pinfunction "1_1") (pintype "passive"))
    )
    (net (code "119") (name "unconnected-(JP6-Pad2)") (class "Default")
      (node (ref "JP6") (pin "2") (pinfunction "2_2") (pintype "passive"))
    )
    (net (code "120") (name "unconnected-(JP6-Pad3)") (class "Default")
      (node (ref "JP6") (pin "3") (pinfunction "3_3") (pintype "passive"))
    )
    (net (code "121") (name "unconnected-(JP6-Pad4)") (class "Default")
      (node (ref "JP6") (pin "4") (pinfunction "4_4") (pintype "passive"))
    )
    (net (code "122") (name "unconnected-(JP6-Pad5)") (class "Default")
      (node (ref "JP6") (pin "5") (pinfunction "5_5") (pintype "passive"))
    )
    (net (code "123") (name "unconnected-(JP6-Pad6)") (class "Default")
      (node (ref "JP6") (pin "6") (pinfunction "6_6") (pintype "passive"))
    )
    (net (code "124") (name "unconnected-(JP6-Pad7)") (class "Default")
      (node (ref "JP6") (pin "7") (pinfunction "7_7") (pintype "passive"))
    )
    (net (code "125") (name "unconnected-(JP6-Pad8)") (class "Default")
      (node (ref "JP6") (pin "8") (pinfunction "8_8") (pintype "passive"))
    )
    (net (code "126") (name "unconnected-(JP6-Pad9)") (class "Default")
      (node (ref "JP6") (pin "9") (pinfunction "9_9") (pintype "passive"))
    )
    (net (code "127") (name "unconnected-(JP6-Pad10)") (class "Default")
      (node (ref "JP6") (pin "10") (pinfunction "10_10") (pintype "passive"))
    )
    (net (code "128") (name "unconnected-(JP6-Pad11)") (class "Default")
      (node (ref "JP6") (pin "11") (pinfunction "11_11") (pintype "passive"))
    )
    (net (code "129") (name "unconnected-(JP7-Pad1)") (class "Default")
      (node (ref "JP7") (pin "1") (pinfunction "1_1") (pintype "passive"))
    )
    (net (code "130") (name "unconnected-(JP7-Pad2)") (class "Default")
      (node (ref "JP7") (pin "2") (pinfunction "2_2") (pintype "passive"))
    )
    (net (code "131") (name "unconnected-(JP7-Pad3)") (class "Default")
      (node (ref "JP7") (pin "3") (pinfunction "3_3") (pintype "passive"))
    )
    (net (code "132") (name "unconnected-(JP7-Pad4)") (class "Default")
      (node (ref "JP7") (pin "4") (pinfunction "4_4") (pintype "passive"))
    )
    (net (code "133") (name "unconnected-(JP7-Pad5)") (class "Default")
      (node (ref "JP7") (pin "5") (pinfunction "5_5") (pintype "passive"))
    )
    (net (code "134") (name "unconnected-(JP7-Pad6)") (class "Default")
      (node (ref "JP7") (pin "6") (pinfunction "6_6") (pintype "passive"))
    )
    (net (code "135") (name "unconnected-(JP7-Pad7)") (class "Default")
      (node (ref "JP7") (pin "7") (pinfunction "7_7") (pintype "passive"))
    )
    (net (code "136") (name "unconnected-(JP7-Pad8)") (class "Default")
      (node (ref "JP7") (pin "8") (pinfunction "8_8") (pintype "passive"))
    )
    (net (code "137") (name "unconnected-(JP7-Pad9)") (class "Default")
      (node (ref "JP7") (pin "9") (pinfunction "9_9") (pintype "passive"))
    )
    (net (code "138") (name "unconnected-(JP7-Pad10)") (class "Default")
      (node (ref "JP7") (pin "10") (pinfunction "10_10") (pintype "passive"))
    )
    (net (code "139") (name "unconnected-(JP7-Pad11)") (class "Default")
      (node (ref "JP7") (pin "11") (pinfunction "11_11") (pintype "passive"))
    )
  )
)
